# WX0_010_981DL_1.net
KiCad netlist of a schematic drawn in Altium Designer
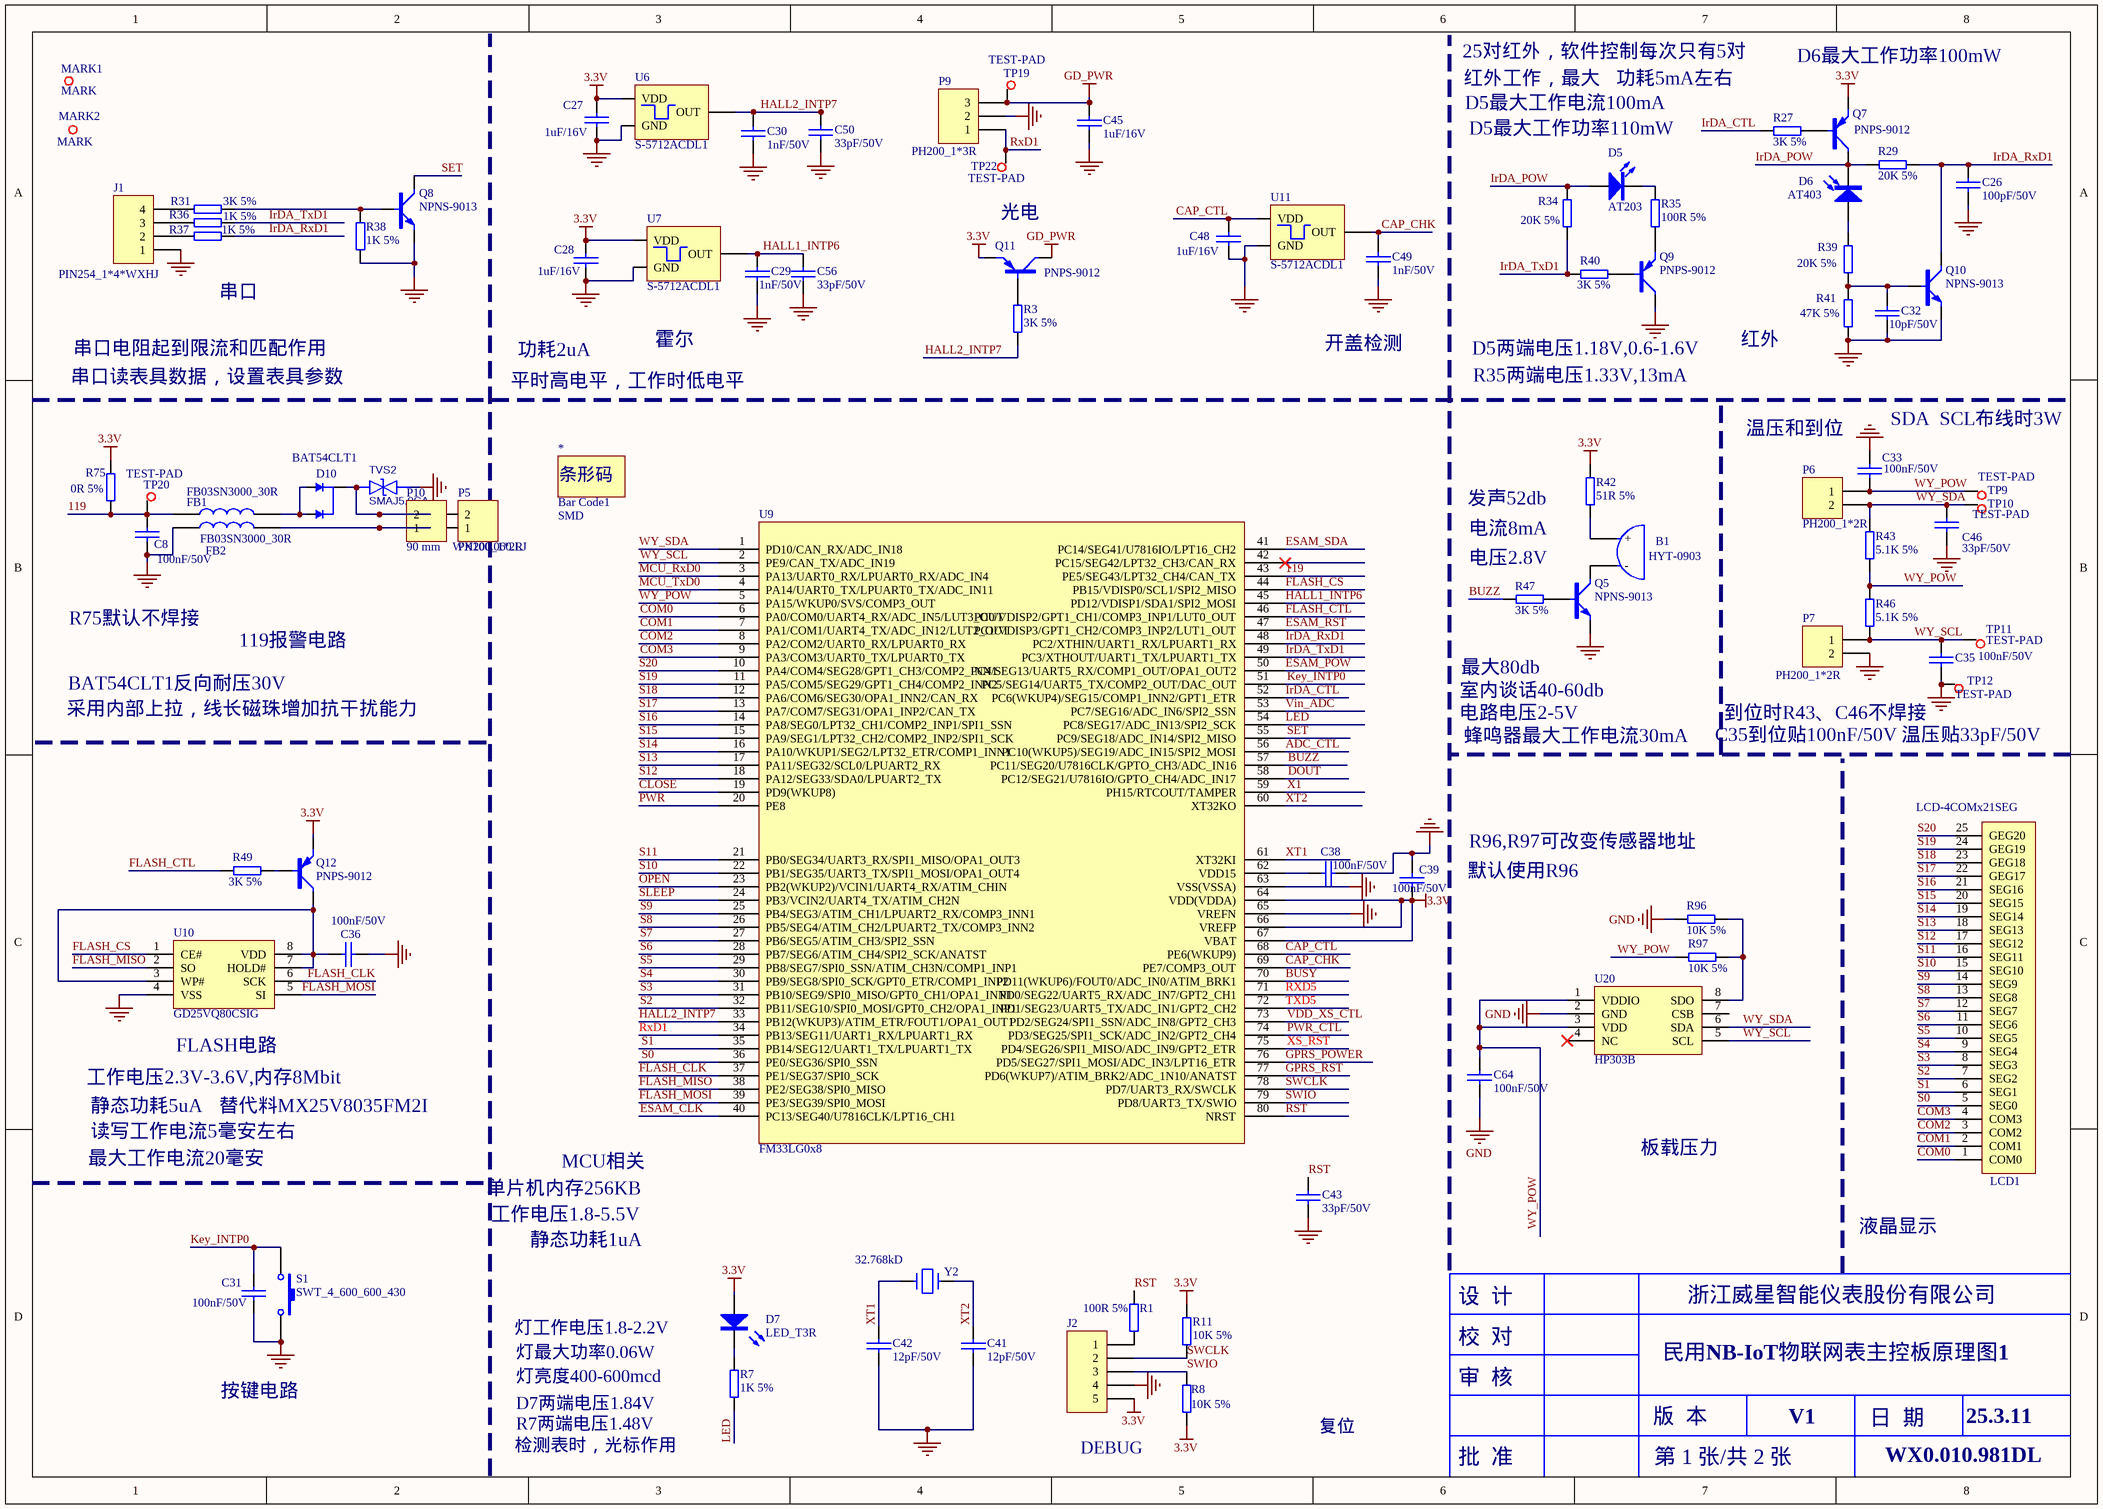
[diagram p0: WX0.010.981DL(1).SchDoc]

(export (version "E")
  (design (tool "Eeschema 10.0.6"))
  (components
    (comp (ref "*")
      (value "Bar Code1")
      (footprint "Bar Code1")
      (description "条形码 ,填充，无需焊接器件")
      (fields (field (name "PART NUMBER") "AD_WXHJ_Bar Code_02") (field (name "SMD/DIP") "SMD"))
      (libsource (lib "Database_Libs2") (part "05_AD_WXHJ_Bar Code_02"))
    )
    (comp (ref "B1")
      (value "HYT-0903")
      (footprint "HYT-0903")
      (description "直插,直径9mm,高5.5mm,5 V,2 V,30 mA,兴化市华宇电子有限公司,HYT-0903")
      (fields (field (name "PART NUMBER") "1010602-0007"))
      (libsource (lib "Database_Libs2") (part "07_HYT-0903"))
    )
    (comp (ref "C8")
      (value "100nF/50V")
      (footprint "CAP0603")
      (description "104pF,50 V,±10%,0603,国巨,CC0603KRX7R9BB104")
      (fields (field (name "PART NUMBER") "101020103-0021"))
      (libsource (lib "Database_Libs2") (part "CC03K7R9_100N"))
    )
    (comp (ref "C26")
      (value "100pF/50V")
      (footprint "CAP0603")
      (description "101pf,50 V,±5%,0603,国巨,CC0603JRNP09BN101")
      (fields (field (name "PART NUMBER") "101020103-0010"))
      (libsource (lib "Database_Libs2") (part "CC03JPO9_101P"))
    )
    (comp (ref "C27")
      (value "1uF/16V")
      (footprint "CAP0603")
      (description "105pF,16 V,±10%,0603,国巨,CC0603KRX7R7BB105")
      (fields (field (name "PART NUMBER") "101020103-0003"))
      (libsource (lib "Database_Libs2") (part "CC03K7R7_1U"))
    )
    (comp (ref "C28")
      (value "1uF/16V")
      (footprint "CAP0603")
      (description "105pF,16 V,±10%,0603,国巨,CC0603KRX7R7BB105")
      (fields (field (name "PART NUMBER") "101020103-0003"))
      (libsource (lib "Database_Libs2") (part "CC03K7R7_1U"))
    )
    (comp (ref "C29")
      (value "1nF/50V")
      (footprint "CAP0603")
      (description "102pF,50 V,±10%,0603,国巨,CC0603KRX7R9BB102")
      (fields (field (name "PART NUMBER") "101020103-0022"))
      (libsource (lib "Database_Libs2") (part "CC03K7R9_1N"))
    )
    (comp (ref "C30")
      (value "1nF/50V")
      (footprint "CAP0603")
      (description "102pF,50 V,±10%,0603,国巨,CC0603KRX7R9BB102")
      (fields (field (name "PART NUMBER") "101020103-0022"))
      (libsource (lib "Database_Libs2") (part "CC03K7R9_1N"))
    )
    (comp (ref "C31")
      (value "100nF/50V")
      (footprint "CAP0603")
      (description "104pF,50 V,±10%,0603,国巨,CC0603KRX7R9BB104")
      (fields (field (name "PART NUMBER") "101020103-0021"))
      (libsource (lib "Database_Libs2") (part "CC03K7R9_100N"))
    )
    (comp (ref "C32")
      (value "10pF/50V")
      (footprint "CAP0603")
      (description "10pF,50 V,±5%,0603,X7R,国巨,CC0603JRNPO9BN100")
      (fields (field (name "PART NUMBER") "101020103-0014"))
      (libsource (lib "Database_Libs2") (part "CC03JPO9_10P"))
    )
    (comp (ref "C33")
      (value "100nF/50V")
      (footprint "CAP0603")
      (description "104pF,50 V,±10%,0603,国巨,CC0603KRX7R9BB104")
      (fields (field (name "PART NUMBER") "101020103-0021"))
      (libsource (lib "Database_Libs2") (part "CC03K7R9_100N"))
    )
    (comp (ref "C35")
      (value "100nF/50V")
      (footprint "CAP0603")
      (description "104pF,50 V,±10%,0603,国巨,CC0603KRX7R9BB104")
      (fields (field (name "PART NUMBER") "101020103-0021"))
      (libsource (lib "Database_Libs2") (part "CC03K7R9_100N"))
    )
    (comp (ref "C36")
      (value "100nF/50V")
      (footprint "CAP0603")
      (description "104pF,50 V,±10%,0603,国巨,CC0603KRX7R9BB104")
      (fields (field (name "PART NUMBER") "101020103-0021"))
      (libsource (lib "Database_Libs2") (part "CC03K7R9_100N"))
    )
    (comp (ref "C38")
      (value "100nF/50V")
      (footprint "CAP0603")
      (description "104pF,50 V,±10%,0603,国巨,CC0603KRX7R9BB104")
      (fields (field (name "PART NUMBER") "101020103-0021"))
      (libsource (lib "Database_Libs2") (part "CC03K7R9_100N"))
    )
    (comp (ref "C39")
      (value "100nF/50V")
      (footprint "CAP0603")
      (description "104pF,50 V,±10%,0603,国巨,CC0603KRX7R9BB104")
      (fields (field (name "PART NUMBER") "101020103-0021"))
      (libsource (lib "Database_Libs2") (part "CC03K7R9_100N"))
    )
    (comp (ref "C41")
      (value "12pF/50V")
      (footprint "CAP0603")
      (description "12P,50 V,±5%,0603,国巨,CC0603JRNPO9BN12")
      (fields (field (name "PART NUMBER") "101020103-0005"))
      (libsource (lib "Database_Libs2") (part "CC03JPO9_12P"))
    )
    (comp (ref "C42")
      (value "12pF/50V")
      (footprint "CAP0603")
      (description "12P,50 V,±5%,0603,国巨,CC0603JRNPO9BN12")
      (fields (field (name "PART NUMBER") "101020103-0005"))
      (libsource (lib "Database_Libs2") (part "CC03JPO9_12P"))
    )
    (comp (ref "C43")
      (value "33pF/50V")
      (footprint "CAP0603")
      (description "33pF,50 V,±10%,0603,国巨,CC0603KRNPO9BN33")
      (fields (field (name "PART NUMBER") "101020103-0027"))
      (libsource (lib "Database_Libs2") (part "CC03KPO9_33P"))
    )
    (comp (ref "C45")
      (value "1uF/16V")
      (footprint "CAP0603")
      (description "105pF,16 V,±10%,0603,国巨,CC0603KRX7R7BB105")
      (fields (field (name "PART NUMBER") "101020103-0003"))
      (libsource (lib "Database_Libs2") (part "CC03K7R7_1U"))
    )
    (comp (ref "C46")
      (value "33pF/50V")
      (footprint "CAP0603")
      (description "33pF,50 V,±10%,0603,国巨,CC0603KRNPO9BN33")
      (fields (field (name "PART NUMBER") "101020103-0027"))
      (libsource (lib "Database_Libs2") (part "CC03KPO9_33P"))
    )
    (comp (ref "C48")
      (value "1uF/16V")
      (footprint "CAP0603")
      (description "105pF,16 V,±10%,0603,国巨,CC0603KRX7R7BB105")
      (fields (field (name "PART NUMBER") "101020103-0003"))
      (libsource (lib "Database_Libs2") (part "CC03K7R7_1U"))
    )
    (comp (ref "C49")
      (value "1nF/50V")
      (footprint "CAP0603")
      (description "102pF,50 V,±10%,0603,国巨,CC0603KRX7R9BB102")
      (fields (field (name "PART NUMBER") "101020103-0022"))
      (libsource (lib "Database_Libs2") (part "CC03K7R9_1N"))
    )
    (comp (ref "C50")
      (value "33pF/50V")
      (footprint "CAP0603")
      (description "33pF,50 V,±10%,0603,国巨,CC0603KRNPO9BN33")
      (fields (field (name "PART NUMBER") "101020103-0027"))
      (libsource (lib "Database_Libs2") (part "CC03KPO9_33P"))
    )
    (comp (ref "C56")
      (value "33pF/50V")
      (footprint "CAP0603")
      (description "33pF,50 V,±10%,0603,国巨,CC0603KRNPO9BN33")
      (fields (field (name "PART NUMBER") "101020103-0027"))
      (libsource (lib "Database_Libs2") (part "CC03KPO9_33P"))
    )
    (comp (ref "C64")
      (value "100nF/50V")
      (footprint "CAP0603")
      (description "104pF,50 V,±10%,0603,国巨,CC0603KRX7R9BB104")
      (fields (field (name "PART NUMBER") "101020103-0021"))
      (libsource (lib "Database_Libs2") (part "CC03K7R9_100N"))
    )
    (comp (ref "D5")
      (value "AT203")
      (footprint "IR_254_532_300")
      (description "DIP-2,φ3,插件,红光,上海品观电子有限公司/可得,AT203")
      (fields (field (name "PART NUMBER") "101040102-0010"))
      (libsource (lib "Database_Libs2") (part "01_AT203"))
    )
    (comp (ref "D6")
      (value "AT403")
      (footprint "IR_254_532_300")
      (description "DIP-2,φ3,插件,红光,上海品观电子有限公司/可得,AT403-PD-01")
      (fields (field (name "PART NUMBER") "101040102-0011"))
      (libsource (lib "Database_Libs2") (part "01_AT403"))
    )
    (comp (ref "D7")
      (value "LED_T3R")
      (footprint "LED2_300")
      (description "圆形插件,3mm 圆形,插件,红光,湖北匡通电子有限公司,3BB4HC")
      (fields (field (name "PART NUMBER") "101040102-0001"))
      (libsource (lib "Database_Libs2") (part "01-LED_T3R"))
    )
    (comp (ref "D10")
      (value "BAT54CLT1")
      (footprint "SOT-23")
      (description "BAT54CLT1，SOT23-3,SOT23-3,0.2 A,0.8 V,30 V,安森美,BAT54CLT1")
      (fields (field (name "PART NUMBER") "101040101-0038"))
      (libsource (lib "Database_Libs2") (part "02_BAT54CLT1"))
    )
    (comp (ref "FB1")
      (value "FB03SN3000_30R")
      (footprint "IND0603")
      (description "chilisin(奇力新),0603,30Ω ±25% @100MHz,150 V,125 ℃,PBY160808T-300Y-N,-55 ℃,不含铅,,,圆盘,30Ω ±25% @100MHz")
      (fields (field (name "PART NUMBER") "109010101-0003"))
      (libsource (lib "Database_Libs2") (part "06_FB03SN3000_30R"))
    )
    (comp (ref "FB2")
      (value "FB03SN3000_30R")
      (footprint "IND0603")
      (description "chilisin(奇力新),0603,30Ω ±25% @100MHz,150 V,125 ℃,PBY160808T-300Y-N,-55 ℃,不含铅,,,圆盘,30Ω ±25% @100MHz")
      (fields (field (name "PART NUMBER") "109010101-0003"))
      (libsource (lib "Database_Libs2") (part "06_FB03SN3000_30R"))
    )
    (comp (ref "J1")
      (value "PIN254_1*4*WXHJ")
      (footprint "PIN254_1*4*WXHJ")
      (description "1*4 ，Φ1.0 ，2.54mm，直脚,无需焊接器件")
      (fields (field (name "PART NUMBER") "AD_WXHJ_PinHeader_01"))
      (libsource (lib "Database_Libs2") (part "PIN254_1*4*WXHJ"))
    )
    (comp (ref "J2")
      (value "PIN254_1*5*WXHJ")
      (footprint "PIN254_1*5*WXHJ")
      (description "1*5 ，Φ1.0 ，2.54mm，直脚,无需焊接器件")
      (fields (field (name "PART NUMBER") "AD_WXHJ_PinHeader_02"))
      (libsource (lib "Database_Libs2") (part "PIN254_1*5*WXHJ"))
    )
    (comp (ref "LCD1")
      (value "GVH21861A-HPP")
      (footprint "LCD_GVH21861A-HPP")
      (fields (field (name "PART NUMBER") "1010801-0028") (field (name "SMD/DIP") "LCD-4COMx21SEG"))
      (libsource (lib "Database_Libs2") (part "03_LCD_GVH21861A-HPP"))
    )
    (comp (ref "MARK1")
      (value "MARK")
      (footprint "MARK")
      (description "MARK点")
      (fields (field (name "PART NUMBER") "AD_WXHJ_MARK_01"))
      (libsource (lib "Database_Libs2") (part "MARK"))
    )
    (comp (ref "MARK2")
      (value "MARK")
      (footprint "MARK")
      (description "MARK点")
      (fields (field (name "PART NUMBER") "AD_WXHJ_MARK_01"))
      (libsource (lib "Database_Libs2") (part "MARK"))
    )
    (comp (ref "P5")
      (value "PH200_1*2R")
      (description "2.0-2AW,直插弯座，2PIN，脚间距2mm，带防翘起,公头,单排,2.0-2AW;直插弯座，2PIN,脚间距2mm，带防翘起")
      (fields (field (name "PART NUMBER") "1010902-0105"))
      (libsource (lib "") (part "PH200_1*2R_1"))
    )
    (comp (ref "P6")
      (value "PH200_1*2R")
      (footprint "PH200_1*2R")
      (description "2.0-2AW,直插弯座，2PIN，脚间距2mm，带防翘起,公头,单排,2.0-2AW;直插弯座，2PIN,脚间距2mm，带防翘起")
      (fields (field (name "PART NUMBER") "1010902-0105"))
      (libsource (lib "Database_Libs2") (part "PH200_1*2R"))
    )
    (comp (ref "P7")
      (value "PH200_1*2R")
      (footprint "PH200_1*2R")
      (description "2.0-2AW,直插弯座，2PIN，脚间距2mm，带防翘起,公头,单排,2.0-2AW;直插弯座，2PIN,脚间距2mm，带防翘起")
      (fields (field (name "PART NUMBER") "1010902-0105"))
      (libsource (lib "Database_Libs2") (part "PH200_1*2R"))
    )
    (comp (ref "P9")
      (value "PH200_1*3R")
      (footprint "PH200_1*3R")
      (description "2.0-3AW,3PIN，2mm脚间距,公头,单排,2.0-3AW；3PIN，脚间距2mm直插弯座带防翘起")
      (fields (field (name "PART NUMBER") "1010902-0104"))
      (libsource (lib "Database_Libs2") (part "PH200_1*3R"))
    )
    (comp (ref "P10")
      (value "90 mm    WX100.060.LJ")
      (footprint "WXHJ_Connect_01")
      (description "电源连接线")
      (fields (field (name "PART NUMBER") "AD_WXHJ_Connect_01"))
      (libsource (lib "Database_Libs2") (part "WXHJ_Connect_01"))
    )
    (comp (ref "Q5")
      (value "NPNS-9013")
      (footprint "SOT-23")
      (description "9013,NPN,SOT-23,长电,S9013")
      (fields (field (name "PART NUMBER") "101040201-0002"))
      (libsource (lib "Database_Libs2") (part "03_NPNS-9013"))
    )
    (comp (ref "Q7")
      (value "PNPS-9012")
      (footprint "SOT-23")
      (description "9012,PNP,SOT-23,JCET;长电,S9012")
      (fields (field (name "PART NUMBER") "101040201-0001"))
      (libsource (lib "Database_Libs2") (part "03_PNPS-9012"))
    )
    (comp (ref "Q8")
      (value "NPNS-9013")
      (footprint "SOT-23")
      (description "9013,NPN,SOT-23,长电,S9013")
      (fields (field (name "PART NUMBER") "101040201-0002"))
      (libsource (lib "Database_Libs2") (part "03_NPNS-9013"))
    )
    (comp (ref "Q9")
      (value "PNPS-9012")
      (footprint "SOT-23")
      (description "9012,PNP,SOT-23,JCET;长电,S9012")
      (fields (field (name "PART NUMBER") "101040201-0001"))
      (libsource (lib "Database_Libs2") (part "03_PNPS-9012"))
    )
    (comp (ref "Q10")
      (value "NPNS-9013")
      (footprint "SOT-23")
      (description "9013,NPN,SOT-23,长电,S9013")
      (fields (field (name "PART NUMBER") "101040201-0002"))
      (libsource (lib "Database_Libs2") (part "03_NPNS-9013"))
    )
    (comp (ref "Q11")
      (value "PNPS-9012")
      (footprint "SOT-23")
      (description "9012,PNP,SOT-23,JCET;长电,S9012")
      (fields (field (name "PART NUMBER") "101040201-0001"))
      (libsource (lib "Database_Libs2") (part "03_PNPS-9012"))
    )
    (comp (ref "Q12")
      (value "PNPS-9012")
      (footprint "SOT-23")
      (description "9012,PNP,SOT-23,JCET;长电,S9012")
      (fields (field (name "PART NUMBER") "101040201-0001"))
      (libsource (lib "Database_Libs2") (part "03_PNPS-9012"))
    )
    (comp (ref "R1")
      (value "100R 5%")
      (footprint "RES0603")
      (description "100R,±5%,1/10W,0603,国巨,RC0603JR-07100RL")
      (fields (field (name "PART NUMBER") "101010103-0022"))
      (libsource (lib "Database_Libs2") (part "RC03J_100R"))
    )
    (comp (ref "R3")
      (value "3K 5%")
      (footprint "RES0603")
      (description "国巨,±5%,0603,,155 ℃,-55 ℃,RC0603JR-073KL,无铅,100 ppm/℃,1/10W,,3K")
      (fields (field (name "PART NUMBER") "101010103-0006"))
      (libsource (lib "Database_Libs2") (part "RC03J_3K"))
    )
    (comp (ref "R7")
      (value "1K 5%")
      (footprint "RES0603")
      (description "1K,±5%,1/10W,0603,国巨,RC0603JR-071KL")
      (fields (field (name "PART NUMBER") "101010103-0008"))
      (libsource (lib "Database_Libs2") (part "RC03J_1K"))
    )
    (comp (ref "R8")
      (value "10K 5%")
      (footprint "RES0603")
      (description "国巨,±5%,0603,,155 ℃,-55 ℃,RC0603JR-0710KL,无铅,200 ppm/℃,1/10W,,10K")
      (fields (field (name "PART NUMBER") "101010103-0003"))
      (libsource (lib "Database_Libs2") (part "RC03J_10K"))
    )
    (comp (ref "R11")
      (value "10K 5%")
      (footprint "RES0603")
      (description "国巨,±5%,0603,,155 ℃,-55 ℃,RC0603JR-0710KL,无铅,200 ppm/℃,1/10W,,10K")
      (fields (field (name "PART NUMBER") "101010103-0003"))
      (libsource (lib "Database_Libs2") (part "RC03J_10K"))
    )
    (comp (ref "R27")
      (value "3K 5%")
      (footprint "RES0603")
      (description "国巨,±5%,0603,,155 ℃,-55 ℃,RC0603JR-073KL,无铅,100 ppm/℃,1/10W,,3K")
      (fields (field (name "PART NUMBER") "101010103-0006"))
      (libsource (lib "Database_Libs2") (part "RC03J_3K"))
    )
    (comp (ref "R29")
      (value "20K 5%")
      (footprint "RES0603")
      (description "国巨,±5%,0603,,155 ℃,-55 ℃,RC0603JR-0720KL,无铅,200 ppm/℃,1/10W,,20K")
      (fields (field (name "PART NUMBER") "101010103-0004"))
      (libsource (lib "Database_Libs2") (part "RC03J_20K"))
    )
    (comp (ref "R31")
      (value "3K 5%")
      (footprint "RES0603")
      (description "国巨,±5%,0603,,155 ℃,-55 ℃,RC0603JR-073KL,无铅,100 ppm/℃,1/10W,,3K")
      (fields (field (name "PART NUMBER") "101010103-0006"))
      (libsource (lib "Database_Libs2") (part "RC03J_3K"))
    )
    (comp (ref "R34")
      (value "20K 5%")
      (footprint "RES0603")
      (description "国巨,±5%,0603,,155 ℃,-55 ℃,RC0603JR-0720KL,无铅,200 ppm/℃,1/10W,,20K")
      (fields (field (name "PART NUMBER") "101010103-0004"))
      (libsource (lib "Database_Libs2") (part "RC03J_20K"))
    )
    (comp (ref "R35")
      (value "100R 5%")
      (footprint "RES0603")
      (description "100R,±5%,1/10W,0603,国巨,RC0603JR-07100RL")
      (fields (field (name "PART NUMBER") "101010103-0022"))
      (libsource (lib "Database_Libs2") (part "RC03J_100R"))
    )
    (comp (ref "R36")
      (value "1K 5%")
      (footprint "RES0603")
      (description "1K,±5%,1/10W,0603,国巨,RC0603JR-071KL")
      (fields (field (name "PART NUMBER") "101010103-0008"))
      (libsource (lib "Database_Libs2") (part "RC03J_1K"))
    )
    (comp (ref "R37")
      (value "1K 5%")
      (footprint "RES0603")
      (description "1K,±5%,1/10W,0603,国巨,RC0603JR-071KL")
      (fields (field (name "PART NUMBER") "101010103-0008"))
      (libsource (lib "Database_Libs2") (part "RC03J_1K"))
    )
    (comp (ref "R38")
      (value "1K 5%")
      (footprint "RES0603")
      (description "1K,±5%,1/10W,0603,国巨,RC0603JR-071KL")
      (fields (field (name "PART NUMBER") "101010103-0008"))
      (libsource (lib "Database_Libs2") (part "RC03J_1K"))
    )
    (comp (ref "R39")
      (value "20K 5%")
      (footprint "RES0603")
      (description "国巨,±5%,0603,,155 ℃,-55 ℃,RC0603JR-0720KL,无铅,200 ppm/℃,1/10W,,20K")
      (fields (field (name "PART NUMBER") "101010103-0004"))
      (libsource (lib "Database_Libs2") (part "RC03J_20K"))
    )
    (comp (ref "R40")
      (value "3K 5%")
      (footprint "RES0603")
      (description "国巨,±5%,0603,,155 ℃,-55 ℃,RC0603JR-073KL,无铅,100 ppm/℃,1/10W,,3K")
      (fields (field (name "PART NUMBER") "101010103-0006"))
      (libsource (lib "Database_Libs2") (part "RC03J_3K"))
    )
    (comp (ref "R41")
      (value "47K 5%")
      (footprint "RES0603")
      (description "47K,±5%,1/10W,0603,国巨,RC0603JR-0747KL")
      (fields (field (name "PART NUMBER") "101010103-0012"))
      (libsource (lib "Database_Libs2") (part "RC03J_47K"))
    )
    (comp (ref "R42")
      (value "51R 5%")
      (footprint "RES0603")
      (description "国巨,±5%,0603,,155 ℃,-55 ℃,RC0603JR-0751RL,无铅,100 ppm/℃,1/10W,,51欧")
      (fields (field (name "PART NUMBER") "101010103-0037"))
      (libsource (lib "Database_Libs2") (part "RC03J_51R"))
    )
    (comp (ref "R43")
      (value "5.1K 5%")
      (footprint "RES0603")
      (description "国巨,±5%,0603,,155 ℃,55 ℃,RC0603JR-075.1KL,无铅,200 ppm/℃,1/10W,,5.1k")
      (fields (field (name "PART NUMBER") "101010103-0015"))
      (libsource (lib "Database_Libs2") (part "RC03J_5.1K"))
    )
    (comp (ref "R46")
      (value "5.1K 5%")
      (footprint "RES0603")
      (description "国巨,±5%,0603,,155 ℃,55 ℃,RC0603JR-075.1KL,无铅,200 ppm/℃,1/10W,,5.1k")
      (fields (field (name "PART NUMBER") "101010103-0015"))
      (libsource (lib "Database_Libs2") (part "RC03J_5.1K"))
    )
    (comp (ref "R47")
      (value "3K 5%")
      (footprint "RES0603")
      (description "国巨,±5%,0603,,155 ℃,-55 ℃,RC0603JR-073KL,无铅,100 ppm/℃,1/10W,,3K")
      (fields (field (name "PART NUMBER") "101010103-0006"))
      (libsource (lib "Database_Libs2") (part "RC03J_3K"))
    )
    (comp (ref "R49")
      (value "3K 5%")
      (footprint "RES0603")
      (description "国巨,±5%,0603,,155 ℃,-55 ℃,RC0603JR-073KL,无铅,100 ppm/℃,1/10W,,3K")
      (fields (field (name "PART NUMBER") "101010103-0006"))
      (libsource (lib "Database_Libs2") (part "RC03J_3K"))
    )
    (comp (ref "R75")
      (value "0R 5%")
      (description "0Ω,±5%,1/4W,1206,国巨,RC1206JR-070RL")
      (fields (field (name "PART NUMBER") "101010101-0013"))
      (libsource (lib "Database_Libs2") (part "RC06J_0R"))
    )
    (comp (ref "R96")
      (value "10K 5%")
      (footprint "RES0603")
      (description "国巨,±5%,0603,,155 ℃,-55 ℃,RC0603JR-071ML,无铅,200 ppm/℃,1/10W,,1M")
      (fields (field (name "PART NUMBER") "101010103-0002"))
      (libsource (lib "Database_Libs2") (part "RC03J_1M"))
    )
    (comp (ref "R97")
      (value "10K 5%")
      (footprint "RES0603")
      (description "国巨,±5%,0603,,155 ℃,-55 ℃,RC0603JR-071ML,无铅,200 ppm/℃,1/10W,,1M")
      (fields (field (name "PART NUMBER") "101010103-0002"))
      (libsource (lib "Database_Libs2") (part "RC03J_1M"))
    )
    (comp (ref "S1")
      (value "SWT_4_600_600_430")
      (footprint "SWT_4_600_600")
      (description "TS-1102,机械轻触,6*6*4.3直插,6*6*4.3直插,乐清市羽欧电子")
      (fields (field (name "PART NUMBER") "1011001-0027"))
      (libsource (lib "Database_Libs2") (part "07_SWT_4_600_600_430"))
    )
    (comp (ref "TP9")
      (value "TEST-PAD")
      (footprint "TEST-PAD")
      (description "单面焊盘测试点")
      (fields (field (name "PART NUMBER") "AD_WXHJ_TEST-PAD_01"))
      (libsource (lib "Database_Libs2") (part "TEST-PAD"))
    )
    (comp (ref "TP10")
      (value "TEST-PAD")
      (footprint "TEST-PAD")
      (description "单面焊盘测试点")
      (fields (field (name "PART NUMBER") "AD_WXHJ_TEST-PAD_01"))
      (libsource (lib "Database_Libs2") (part "TEST-PAD"))
    )
    (comp (ref "TP11")
      (value "TEST-PAD")
      (footprint "TEST-PAD")
      (description "单面焊盘测试点")
      (fields (field (name "PART NUMBER") "AD_WXHJ_TEST-PAD_01"))
      (libsource (lib "Database_Libs2") (part "TEST-PAD"))
    )
    (comp (ref "TP12")
      (value "TEST-PAD")
      (footprint "TEST-PAD")
      (description "单面焊盘测试点")
      (fields (field (name "PART NUMBER") "AD_WXHJ_TEST-PAD_01"))
      (libsource (lib "Database_Libs2") (part "TEST-PAD"))
    )
    (comp (ref "TP19")
      (value "TEST-PAD")
      (footprint "TEST-PAD")
      (description "单面焊盘测试点")
      (fields (field (name "PART NUMBER") "AD_WXHJ_TEST-PAD_01"))
      (libsource (lib "Database_Libs2") (part "TEST-PAD"))
    )
    (comp (ref "TP20")
      (value "TEST-PAD")
      (footprint "TEST-PAD")
      (description "单面焊盘测试点")
      (fields (field (name "PART NUMBER") "AD_WXHJ_TEST-PAD_01"))
      (libsource (lib "Database_Libs2") (part "TEST-PAD"))
    )
    (comp (ref "TP22")
      (value "TEST-PAD")
      (footprint "TEST-PAD")
      (description "单面焊盘测试点")
      (fields (field (name "PART NUMBER") "AD_WXHJ_TEST-PAD_01"))
      (libsource (lib "Database_Libs2") (part "TEST-PAD"))
    )
    (comp (ref "TVS2")
      (value "SMAJ5.0CA")
      (footprint "SMAJ5.0CA")
      (fields (field (name "BOM_SUPPLIER PART") "C693487") (field (name "CONTRIBUTOR") "LCSC"))
      (libsource (lib "Discrete_WX") (part "SMAJ5.0CA_C693487"))
    )
    (comp (ref "U6")
      (value "S-5712ACDL1")
      (footprint "SOT-23")
      (description "S-5712ACDL1,SOT23-3,3.5 V,1.6 V,2 uA,精工电子,S-5712ACDL1")
      (fields (field (name "PART NUMBER") "1010504-0002"))
      (libsource (lib "Database_Libs2") (part "01_S-5712ACDL1"))
    )
    (comp (ref "U7")
      (value "S-5712ACDL1")
      (footprint "SOT-23")
      (description "S-5712ACDL1,SOT23-3,3.5 V,1.6 V,2 uA,精工电子,S-5712ACDL1")
      (fields (field (name "PART NUMBER") "1010504-0002"))
      (libsource (lib "Database_Libs2") (part "01_S-5712ACDL1"))
    )
    (comp (ref "U9") (value "FM33LG0x8") (footprint "LQFP80") (libsource (lib "FM_MCU") (part "FM33LG0x8")))
    (comp (ref "U10")
      (value "GD25VQ80CSIG")
      (footprint "SOP-8L-200MIL")
      (description "GD25VQ80CSIG,SOP8 208mil,北京兆易创新科技股份有限公司,GD25VQ80CSIG")
      (fields (field (name "PART NUMBER") "101050101-0165"))
      (libsource (lib "Database_Libs2") (part "04_GD25VQ80CSIG"))
    )
    (comp (ref "U11")
      (value "S-5712ACDL1")
      (footprint "SOT-23")
      (description "S-5712ACDL1,SOT23-3,3.5 V,1.6 V,2 uA,精工电子,S-5712ACDL1")
      (fields (field (name "PART NUMBER") "1010504-0002"))
      (libsource (lib "Database_Libs2") (part "01_S-5712ACDL1"))
    )
    (comp (ref "U20") (value "HP303B") (footprint "LGA_8") (libsource (lib "Schlib2") (part "HP303B")))
    (comp (ref "Y2")
      (value "32.768kD")
      (footprint "SMD-3215_2P")
      (fields (field (name "PART NUMBER") "1010601-0020"))
      (libsource (lib "Database_Libs2") (part "04_XTALSG12MD_32.768kD"))
    )
  )
  (nets
    (net (code "1") (name "/119") (class "Default")
      (node (ref "C8") (pin "1") (pinfunction "1_1") (pintype "passive"))
      (node (ref "FB1") (pin "1") (pinfunction "1_1") (pintype "passive"))
      (node (ref "R75") (pin "1") (pinfunction "1_1") (pintype "passive"))
      (node (ref "TP20") (pin "1") (pinfunction "1_1") (pintype "passive"))
      (node (ref "U9") (pin "43") (pinfunction "PE5/SEG43/LPT32_CH4/CAN_TX_43") (pintype "passive"))
    )
    (net (code "2") (name "/ADC_CTL") (class "Default")
      (node (ref "U9") (pin "56") (pinfunction "PC10(WKUP5)/SEG19/ADC_IN15/SPI2_MOSI_56") (pintype "passive"))
    )
    (net (code "3") (name "/BUSY") (class "Default")
      (node (ref "U9") (pin "70") (pinfunction "PD11(WKUP6)/FOUT0/ADC_IN0/ATIM_BRK1_70") (pintype "passive"))
    )
    (net (code "4") (name "/BUZZ") (class "Default")
      (node (ref "R47") (pin "1") (pinfunction "1_1") (pintype "passive"))
      (node (ref "U9") (pin "57") (pinfunction "PC11/SEG20/U7816CLK/GPTO_CH3/ADC_IN16_57") (pintype "passive"))
    )
    (net (code "5") (name "/CAP_CHK") (class "Default")
      (node (ref "C49") (pin "1") (pinfunction "1_1") (pintype "passive"))
      (node (ref "U11") (pin "2") (pinfunction "OUT_2") (pintype "passive"))
      (node (ref "U9") (pin "69") (pinfunction "PE7/COMP3_OUT_69") (pintype "passive"))
    )
    (net (code "6") (name "/CAP_CTL") (class "Default")
      (node (ref "C48") (pin "1") (pinfunction "1_1") (pintype "passive"))
      (node (ref "U11") (pin "1") (pinfunction "VDD_1") (pintype "passive"))
      (node (ref "U9") (pin "68") (pinfunction "PE6(WKUP9)_68") (pintype "passive"))
    )
    (net (code "7") (name "/CLOSE") (class "Default")
      (node (ref "U9") (pin "19") (pinfunction "PD9(WKUP8)_19") (pintype "passive"))
    )
    (net (code "8") (name "/COM0") (class "Default")
      (node (ref "LCD1") (pin "1") (pinfunction "COM0_1") (pintype "passive"))
      (node (ref "U9") (pin "6") (pinfunction "PA0/COM0/UART4_RX/ADC_IN5/LUT3_OUT_6") (pintype "passive"))
    )
    (net (code "9") (name "/COM1") (class "Default")
      (node (ref "LCD1") (pin "2") (pinfunction "COM1_2") (pintype "passive"))
      (node (ref "U9") (pin "7") (pinfunction "PA1/COM1/UART4_TX/ADC_IN12/LUT2_OUT_7") (pintype "passive"))
    )
    (net (code "10") (name "/COM2") (class "Default")
      (node (ref "LCD1") (pin "3") (pinfunction "COM2_3") (pintype "passive"))
      (node (ref "U9") (pin "8") (pinfunction "PA2/COM2/UART0_RX/LPUART0_RX_8") (pintype "passive"))
    )
    (net (code "11") (name "/COM3") (class "Default")
      (node (ref "LCD1") (pin "4") (pinfunction "COM3_4") (pintype "passive"))
      (node (ref "U9") (pin "9") (pinfunction "PA3/COM3/UART0_TX/LPUART0_TX_9") (pintype "passive"))
    )
    (net (code "12") (name "/DOUT") (class "Default")
      (node (ref "U9") (pin "58") (pinfunction "PC12/SEG21/U7816IO/GPTO_CH4/ADC_IN17_58") (pintype "passive"))
    )
    (net (code "13") (name "/ESAM_CLK") (class "Default")
      (node (ref "U9") (pin "40") (pinfunction "PC13/SEG40/U7816CLK/LPT16_CH1_40") (pintype "passive"))
    )
    (net (code "14") (name "/ESAM_POW") (class "Default")
      (node (ref "U9") (pin "50") (pinfunction "PC4/SEG13/UART5_RX/COMP1_OUT/OPA1_OUT2_50") (pintype "passive"))
    )
    (net (code "15") (name "/ESAM_RST") (class "Default")
      (node (ref "U9") (pin "47") (pinfunction "PC1/VDISP3/GPT1_CH2/COMP3_INP2/LUT1_OUT_47") (pintype "passive"))
    )
    (net (code "16") (name "/ESAM_SDA") (class "Default")
      (node (ref "U9") (pin "41") (pinfunction "PC14/SEG41/U7816IO/LPT16_CH2_41") (pintype "passive"))
    )
    (net (code "17") (name "/FLASH_CLK") (class "Default")
      (node (ref "U10") (pin "6") (pinfunction "SCK_6") (pintype "passive"))
      (node (ref "U9") (pin "37") (pinfunction "PE1/SEG37/SPI0_SCK_37") (pintype "passive"))
    )
    (net (code "18") (name "/FLASH_CS") (class "Default")
      (node (ref "U10") (pin "1") (pinfunction "CE#_1") (pintype "passive"))
      (node (ref "U9") (pin "44") (pinfunction "PB15/VDISP0/SCL1/SPI2_MISO_44") (pintype "passive"))
    )
    (net (code "19") (name "/FLASH_CTL") (class "Default")
      (node (ref "R49") (pin "1") (pinfunction "1_1") (pintype "passive"))
      (node (ref "U9") (pin "46") (pinfunction "PC0/VDISP2/GPT1_CH1/COMP3_INP1/LUT0_OUT_46") (pintype "passive"))
    )
    (net (code "20") (name "/FLASH_MISO") (class "Default")
      (node (ref "U10") (pin "2") (pinfunction "SO_2") (pintype "passive"))
      (node (ref "U9") (pin "38") (pinfunction "PE2/SEG38/SPI0_MISO_38") (pintype "passive"))
    )
    (net (code "21") (name "/FLASH_MOSI") (class "Default")
      (node (ref "U10") (pin "5") (pinfunction "SI_5") (pintype "passive"))
      (node (ref "U9") (pin "39") (pinfunction "PE3/SEG39/SPI0_MOSI_39") (pintype "passive"))
    )
    (net (code "22") (name "/GPRS_POWER") (class "Default")
      (node (ref "U9") (pin "76") (pinfunction "PD5/SEG27/SPI1_MOSI/ADC_IN3/LPT16_ETR_76") (pintype "passive"))
    )
    (net (code "23") (name "/GPRS_RST") (class "Default")
      (node (ref "U9") (pin "77") (pinfunction "PD6(WKUP7)/ATIM_BRK2/ADC_1N10/ANATST_77") (pintype "passive"))
    )
    (net (code "24") (name "/HALL1_INTP6") (class "Default")
      (node (ref "C29") (pin "1") (pinfunction "1_1") (pintype "passive"))
      (node (ref "C56") (pin "1") (pinfunction "1_1") (pintype "passive"))
      (node (ref "U7") (pin "2") (pinfunction "OUT_2") (pintype "passive"))
      (node (ref "U9") (pin "45") (pinfunction "PD12/VDISP1/SDA1/SPI2_MOSI_45") (pintype "passive"))
    )
    (net (code "25") (name "/HALL2_INTP7") (class "Default")
      (node (ref "C30") (pin "1") (pinfunction "1_1") (pintype "passive"))
      (node (ref "C50") (pin "1") (pinfunction "1_1") (pintype "passive"))
      (node (ref "R3") (pin "1") (pinfunction "1_1") (pintype "passive"))
      (node (ref "U6") (pin "2") (pinfunction "OUT_2") (pintype "passive"))
      (node (ref "U9") (pin "33") (pinfunction "PB12(WKUP3)/ATIM_ETR/FOUT1/OPA1_OUT1_33") (pintype "passive"))
    )
    (net (code "26") (name "/IrDA_CTL") (class "Default")
      (node (ref "R27") (pin "1") (pinfunction "1_1") (pintype "passive"))
      (node (ref "U9") (pin "52") (pinfunction "PC6(WKUP4)/SEG15/COMP1_INN2/GPT1_ETR_52") (pintype "passive"))
    )
    (net (code "27") (name "/IrDA_POW") (class "Default")
      (node (ref "D5") (pin "1") (pinfunction "A_1") (pintype "passive"))
      (node (ref "D6") (pin "2") (pinfunction "K_2") (pintype "passive"))
      (node (ref "Q7") (pin "3") (pinfunction "C_3") (pintype "passive"))
      (node (ref "R29") (pin "1") (pinfunction "1_1") (pintype "passive"))
      (node (ref "R34") (pin "2") (pinfunction "2_2") (pintype "passive"))
    )
    (net (code "28") (name "/IrDA_RxD1") (class "Default")
      (node (ref "C26") (pin "1") (pinfunction "1_1") (pintype "passive"))
      (node (ref "Q10") (pin "3") (pinfunction "C_3") (pintype "passive"))
      (node (ref "R29") (pin "2") (pinfunction "2_2") (pintype "passive"))
      (node (ref "R37") (pin "2") (pinfunction "2_2") (pintype "passive"))
      (node (ref "U9") (pin "48") (pinfunction "PC2/XTHIN/UART1_RX/LPUART1_RX_48") (pintype "passive"))
    )
    (net (code "29") (name "/IrDA_TxD1") (class "Default")
      (node (ref "R34") (pin "1") (pinfunction "1_1") (pintype "passive"))
      (node (ref "R36") (pin "2") (pinfunction "2_2") (pintype "passive"))
      (node (ref "R40") (pin "1") (pinfunction "1_1") (pintype "passive"))
      (node (ref "U9") (pin "49") (pinfunction "PC3/XTHOUT/UART1_TX/LPUART1_TX_49") (pintype "passive"))
    )
    (net (code "30") (name "/Key_INTP0") (class "Default")
      (node (ref "C31") (pin "1") (pinfunction "1_1") (pintype "passive"))
      (node (ref "S1") (pin "1") (pinfunction "1_1") (pintype "passive"))
      (node (ref "U9") (pin "51") (pinfunction "PC5/SEG14/UART5_TX/COMP2_OUT/DAC_OUT_51") (pintype "passive"))
    )
    (net (code "31") (name "/LED") (class "Default")
      (node (ref "R7") (pin "1") (pinfunction "1_1") (pintype "passive"))
      (node (ref "U9") (pin "54") (pinfunction "PC8/SEG17/ADC_IN13/SPI2_SCK_54") (pintype "passive"))
    )
    (net (code "32") (name "/MCU_RxD0") (class "Default")
      (node (ref "U9") (pin "3") (pinfunction "PA13/UART0_RX/LPUART0_RX/ADC_IN4_3") (pintype "passive"))
    )
    (net (code "33") (name "/MCU_TxD0") (class "Default")
      (node (ref "U9") (pin "4") (pinfunction "PA14/UART0_TX/LPUART0_TX/ADC_IN11_4") (pintype "passive"))
    )
    (net (code "34") (name "/OPEN") (class "Default")
      (node (ref "U9") (pin "23") (pinfunction "PB2(WKUP2)/VCIN1/UART4_RX/ATIM_CHIN_23") (pintype "passive"))
    )
    (net (code "35") (name "/PWR") (class "Default")
      (node (ref "U9") (pin "20") (pinfunction "PE8_20") (pintype "passive"))
    )
    (net (code "36") (name "/PWR_CTL") (class "Default")
      (node (ref "U9") (pin "74") (pinfunction "PD3/SEG25/SPI1_SCK/ADC_IN2/GPT2_CH4_74") (pintype "passive"))
    )
    (net (code "37") (name "/RST") (class "Default")
      (node (ref "C43") (pin "1") (pinfunction "1_1") (pintype "passive"))
      (node (ref "R1") (pin "1") (pinfunction "1_1") (pintype "passive"))
      (node (ref "U9") (pin "80") (pinfunction "NRST_80") (pintype "passive"))
    )
    (net (code "38") (name "/RXD5") (class "Default")
      (node (ref "U9") (pin "71") (pinfunction "PD0/SEG22/UART5_RX/ADC_IN7/GPT2_CH1_71") (pintype "passive"))
    )
    (net (code "39") (name "/RxD1") (class "Default")
      (node (ref "P9") (pin "1") (pinfunction "1_1") (pintype "passive"))
      (node (ref "TP22") (pin "1") (pinfunction "1_1") (pintype "passive"))
      (node (ref "U9") (pin "34") (pinfunction "PB13/SEG11/UART1_RX/LPUART1_RX_34") (pintype "passive"))
    )
    (net (code "40") (name "/S0") (class "Default")
      (node (ref "LCD1") (pin "5") (pinfunction "SEG0_5") (pintype "passive"))
      (node (ref "U9") (pin "36") (pinfunction "PE0/SEG36/SPI0_SSN_36") (pintype "passive"))
    )
    (net (code "41") (name "/S1") (class "Default")
      (node (ref "LCD1") (pin "6") (pinfunction "SEG1_6") (pintype "passive"))
      (node (ref "U9") (pin "35") (pinfunction "PB14/SEG12/UART1_TX/LPUART1_TX_35") (pintype "passive"))
    )
    (net (code "42") (name "/S2") (class "Default")
      (node (ref "LCD1") (pin "7") (pinfunction "SEG2_7") (pintype "passive"))
      (node (ref "U9") (pin "32") (pinfunction "PB11/SEG10/SPI0_MOSI/GPT0_CH2/OPA1_INP1_32") (pintype "passive"))
    )
    (net (code "43") (name "/S3") (class "Default")
      (node (ref "LCD1") (pin "8") (pinfunction "SEG3_8") (pintype "passive"))
      (node (ref "U9") (pin "31") (pinfunction "PB10/SEG9/SPI0_MISO/GPT0_CH1/OPA1_INN1_31") (pintype "passive"))
    )
    (net (code "44") (name "/S4") (class "Default")
      (node (ref "LCD1") (pin "9") (pinfunction "SEG4_9") (pintype "passive"))
      (node (ref "U9") (pin "30") (pinfunction "PB9/SEG8/SPI0_SCK/GPT0_ETR/COMP1_INP2_30") (pintype "passive"))
    )
    (net (code "45") (name "/S5") (class "Default")
      (node (ref "LCD1") (pin "10") (pinfunction "SEG5_10") (pintype "passive"))
      (node (ref "U9") (pin "29") (pinfunction "PB8/SEG7/SPI0_SSN/ATIM_CH3N/COMP1_INP1_29") (pintype "passive"))
    )
    (net (code "46") (name "/S6") (class "Default")
      (node (ref "LCD1") (pin "11") (pinfunction "SEG6_11") (pintype "passive"))
      (node (ref "U9") (pin "28") (pinfunction "PB7/SEG6/ATIM_CH4/SPI2_SCK/ANATST_28") (pintype "passive"))
    )
    (net (code "47") (name "/S7") (class "Default")
      (node (ref "LCD1") (pin "12") (pinfunction "SEG7_12") (pintype "passive"))
      (node (ref "U9") (pin "27") (pinfunction "PB6/SEG5/ATIM_CH3/SPI2_SSN_27") (pintype "passive"))
    )
    (net (code "48") (name "/S8") (class "Default")
      (node (ref "LCD1") (pin "13") (pinfunction "SEG8_13") (pintype "passive"))
      (node (ref "U9") (pin "26") (pinfunction "PB5/SEG4/ATIM_CH2/LPUART2_TX/COMP3_INN2_26") (pintype "passive"))
    )
    (net (code "49") (name "/S9") (class "Default")
      (node (ref "LCD1") (pin "14") (pinfunction "SEG9_14") (pintype "passive"))
      (node (ref "U9") (pin "25") (pinfunction "PB4/SEG3/ATIM_CH1/LPUART2_RX/COMP3_INN1_25") (pintype "passive"))
    )
    (net (code "50") (name "/S10") (class "Default")
      (node (ref "LCD1") (pin "15") (pinfunction "SEG10_15") (pintype "passive"))
      (node (ref "U9") (pin "22") (pinfunction "PB1/SEG35/UART3_TX/SPI1_MOSI/OPA1_OUT4_22") (pintype "passive"))
    )
    (net (code "51") (name "/S11") (class "Default")
      (node (ref "LCD1") (pin "16") (pinfunction "SEG11_16") (pintype "passive"))
      (node (ref "U9") (pin "21") (pinfunction "PB0/SEG34/UART3_RX/SPI1_MISO/OPA1_OUT3_21") (pintype "passive"))
    )
    (net (code "52") (name "/S12") (class "Default")
      (node (ref "LCD1") (pin "17") (pinfunction "SEG12_17") (pintype "passive"))
      (node (ref "U9") (pin "18") (pinfunction "PA12/SEG33/SDA0/LPUART2_TX_18") (pintype "passive"))
    )
    (net (code "53") (name "/S13") (class "Default")
      (node (ref "LCD1") (pin "18") (pinfunction "SEG13_18") (pintype "passive"))
      (node (ref "U9") (pin "17") (pinfunction "PA11/SEG32/SCL0/LPUART2_RX_17") (pintype "passive"))
    )
    (net (code "54") (name "/S14") (class "Default")
      (node (ref "LCD1") (pin "19") (pinfunction "SEG14_19") (pintype "passive"))
      (node (ref "U9") (pin "16") (pinfunction "PA10/WKUP1/SEG2/LPT32_ETR/COMP1_INN1_16") (pintype "passive"))
    )
    (net (code "55") (name "/S15") (class "Default")
      (node (ref "LCD1") (pin "20") (pinfunction "SEG15_20") (pintype "passive"))
      (node (ref "U9") (pin "15") (pinfunction "PA9/SEG1/LPT32_CH2/COMP2_INP2/SPI1_SCK_15") (pintype "passive"))
    )
    (net (code "56") (name "/S16") (class "Default")
      (node (ref "LCD1") (pin "21") (pinfunction "SEG16_21") (pintype "passive"))
      (node (ref "U9") (pin "14") (pinfunction "PA8/SEG0/LPT32_CH1/COMP2_INP1/SPI1_SSN_14") (pintype "passive"))
    )
    (net (code "57") (name "/S17") (class "Default")
      (node (ref "LCD1") (pin "22") (pinfunction "GEG17_22") (pintype "passive"))
      (node (ref "U9") (pin "13") (pinfunction "PA7/COM7/SEG31/OPA1_INP2/CAN_TX_13") (pintype "passive"))
    )
    (net (code "58") (name "/S18") (class "Default")
      (node (ref "LCD1") (pin "23") (pinfunction "GEG18_23") (pintype "passive"))
      (node (ref "U9") (pin "12") (pinfunction "PA6/COM6/SEG30/OPA1_INN2/CAN_RX_12") (pintype "passive"))
    )
    (net (code "59") (name "/S19") (class "Default")
      (node (ref "LCD1") (pin "24") (pinfunction "GEG19_24") (pintype "passive"))
      (node (ref "U9") (pin "11") (pinfunction "PA5/COM5/SEG29/GPT1_CH4/COMP2_INN2_11") (pintype "passive"))
    )
    (net (code "60") (name "/S20") (class "Default")
      (node (ref "LCD1") (pin "25") (pinfunction "GEG20_25") (pintype "passive"))
      (node (ref "U9") (pin "10") (pinfunction "PA4/COM4/SEG28/GPT1_CH3/COMP2_INN1_10") (pintype "passive"))
    )
    (net (code "61") (name "/SET") (class "Default")
      (node (ref "Q8") (pin "3") (pinfunction "C_3") (pintype "passive"))
      (node (ref "U9") (pin "55") (pinfunction "PC9/SEG18/ADC_IN14/SPI2_MISO_55") (pintype "passive"))
    )
    (net (code "62") (name "/SLEEP") (class "Default")
      (node (ref "U9") (pin "24") (pinfunction "PB3/VCIN2/UART4_TX/ATIM_CH2N_24") (pintype "passive"))
    )
    (net (code "63") (name "/SWCLK") (class "Default")
      (node (ref "J2") (pin "2") (pinfunction "2_2") (pintype "passive"))
      (node (ref "R11") (pin "2") (pinfunction "2_2") (pintype "passive"))
      (node (ref "U9") (pin "78") (pinfunction "PD7/UART3_RX/SWCLK_78") (pintype "passive"))
    )
    (net (code "64") (name "/SWIO") (class "Default")
      (node (ref "J2") (pin "3") (pinfunction "3_3") (pintype "passive"))
      (node (ref "R8") (pin "2") (pinfunction "2_2") (pintype "passive"))
      (node (ref "U9") (pin "79") (pinfunction "PD8/UART3_TX/SWIO_79") (pintype "passive"))
    )
    (net (code "65") (name "/TXD5") (class "Default")
      (node (ref "U9") (pin "72") (pinfunction "PD1/SEG23/UART5_TX/ADC_IN1/GPT2_CH2_72") (pintype "passive"))
    )
    (net (code "66") (name "/VDD_XS_CTL") (class "Default")
      (node (ref "U9") (pin "73") (pinfunction "PD2/SEG24/SPI1_SSN/ADC_IN8/GPT2_CH3_73") (pintype "passive"))
    )
    (net (code "67") (name "/Vin_ADC") (class "Default")
      (node (ref "U9") (pin "53") (pinfunction "PC7/SEG16/ADC_IN6/SPI2_SSN_53") (pintype "passive"))
    )
    (net (code "68") (name "/WY_POW") (class "Default")
      (node (ref "C33") (pin "2") (pinfunction "2_2") (pintype "passive"))
      (node (ref "C64") (pin "2") (pinfunction "2_2") (pintype "passive"))
      (node (ref "P6") (pin "1") (pinfunction "1_1") (pintype "passive"))
      (node (ref "R43") (pin "1") (pinfunction "1_1") (pintype "passive"))
      (node (ref "R46") (pin "2") (pinfunction "2_2") (pintype "passive"))
      (node (ref "R97") (pin "2") (pinfunction "2_2") (pintype "passive"))
      (node (ref "TP9") (pin "1") (pinfunction "1_1") (pintype "passive"))
      (node (ref "U20") (pin "1") (pinfunction "VDDIO_1") (pintype "passive"))
      (node (ref "U20") (pin "3") (pinfunction "VDD_3") (pintype "passive"))
      (node (ref "U9") (pin "5") (pinfunction "PA15/WKUP0/SVS/COMP3_OUT_5") (pintype "passive"))
    )
    (net (code "69") (name "/WY_SCL") (class "Default")
      (node (ref "C35") (pin "1") (pinfunction "1_1") (pintype "passive"))
      (node (ref "P7") (pin "1") (pinfunction "1_1") (pintype "passive"))
      (node (ref "R46") (pin "1") (pinfunction "1_1") (pintype "passive"))
      (node (ref "TP11") (pin "1") (pinfunction "1_1") (pintype "passive"))
      (node (ref "U20") (pin "5") (pinfunction "SCL_5") (pintype "passive"))
      (node (ref "U9") (pin "2") (pinfunction "PE9/CAN_TX/ADC_IN19_2") (pintype "passive"))
    )
    (net (code "70") (name "/WY_SDA") (class "Default")
      (node (ref "C46") (pin "1") (pinfunction "1_1") (pintype "passive"))
      (node (ref "P6") (pin "2") (pinfunction "2_2") (pintype "passive"))
      (node (ref "R43") (pin "2") (pinfunction "2_2") (pintype "passive"))
      (node (ref "TP10") (pin "1") (pinfunction "1_1") (pintype "passive"))
      (node (ref "U20") (pin "6") (pinfunction "SDA_6") (pintype "passive"))
      (node (ref "U9") (pin "1") (pinfunction "PD10/CAN_RX/ADC_IN18_1") (pintype "passive"))
    )
    (net (code "71") (name "/X1") (class "Default")
      (node (ref "U9") (pin "59") (pinfunction "PH15/RTCOUT/TAMPER_59") (pintype "passive"))
    )
    (net (code "72") (name "/XS_RST") (class "Default")
      (node (ref "U9") (pin "75") (pinfunction "PD4/SEG26/SPI1_MISO/ADC_IN9/GPT2_ETR_75") (pintype "passive"))
    )
    (net (code "73") (name "/XT1") (class "Default")
      (node (ref "C42") (pin "1") (pinfunction "1_1") (pintype "passive"))
      (node (ref "U9") (pin "61") (pinfunction "XT32KI_61") (pintype "passive"))
      (node (ref "Y2") (pin "1") (pinfunction "1_1") (pintype "passive"))
    )
    (net (code "74") (name "/XT2") (class "Default")
      (node (ref "C41") (pin "2") (pinfunction "2_2") (pintype "passive"))
      (node (ref "U9") (pin "60") (pinfunction "XT32KO_60") (pintype "passive"))
      (node (ref "Y2") (pin "2") (pinfunction "2_2") (pintype "passive"))
    )
    (net (code "75") (name "3.3V") (class "Default")
      (node (ref "C27") (pin "1") (pinfunction "1_1") (pintype "passive"))
      (node (ref "C28") (pin "1") (pinfunction "1_1") (pintype "passive"))
      (node (ref "C39") (pin "2") (pinfunction "2_2") (pintype "passive"))
      (node (ref "D7") (pin "1") (pinfunction "1_1") (pintype "passive"))
      (node (ref "J2") (pin "5") (pinfunction "5_5") (pintype "passive"))
      (node (ref "Q11") (pin "2") (pinfunction "E_2") (pintype "passive"))
      (node (ref "Q12") (pin "2") (pinfunction "E_2") (pintype "passive"))
      (node (ref "Q7") (pin "2") (pinfunction "E_2") (pintype "passive"))
      (node (ref "R11") (pin "1") (pinfunction "1_1") (pintype "passive"))
      (node (ref "R42") (pin "2") (pinfunction "2_2") (pintype "passive"))
      (node (ref "R75") (pin "2") (pinfunction "2_2") (pintype "passive"))
      (node (ref "R8") (pin "1") (pinfunction "1_1") (pintype "passive"))
      (node (ref "U6") (pin "1") (pinfunction "VDD_1") (pintype "passive"))
      (node (ref "U7") (pin "1") (pinfunction "VDD_1") (pintype "passive"))
      (node (ref "U9") (pin "64") (pinfunction "VDD(VDDA)_64") (pintype "passive"))
      (node (ref "U9") (pin "66") (pinfunction "VREFP_66") (pintype "passive"))
      (node (ref "U9") (pin "67") (pinfunction "VBAT_67") (pintype "passive"))
    )
    (net (code "76") (name "GD_PWR") (class "Default")
      (node (ref "C45") (pin "1") (pinfunction "1_1") (pintype "passive"))
      (node (ref "P9") (pin "3") (pinfunction "3_3") (pintype "passive"))
      (node (ref "Q11") (pin "3") (pinfunction "C_3") (pintype "passive"))
      (node (ref "TP19") (pin "1") (pinfunction "1_1") (pintype "passive"))
    )
    (net (code "77") (name "GND") (class "Default")
      (node (ref "C26") (pin "2") (pinfunction "2_2") (pintype "passive"))
      (node (ref "C27") (pin "2") (pinfunction "2_2") (pintype "passive"))
      (node (ref "C28") (pin "2") (pinfunction "2_2") (pintype "passive"))
      (node (ref "C29") (pin "2") (pinfunction "2_2") (pintype "passive"))
      (node (ref "C30") (pin "2") (pinfunction "2_2") (pintype "passive"))
      (node (ref "C31") (pin "2") (pinfunction "2_2") (pintype "passive"))
      (node (ref "C32") (pin "2") (pinfunction "2_2") (pintype "passive"))
      (node (ref "C33") (pin "1") (pinfunction "1_1") (pintype "passive"))
      (node (ref "C35") (pin "2") (pinfunction "2_2") (pintype "passive"))
      (node (ref "C36") (pin "2") (pinfunction "2_2") (pintype "passive"))
      (node (ref "C38") (pin "2") (pinfunction "2_2") (pintype "passive"))
      (node (ref "C39") (pin "1") (pinfunction "1_1") (pintype "passive"))
      (node (ref "C41") (pin "1") (pinfunction "1_1") (pintype "passive"))
      (node (ref "C42") (pin "2") (pinfunction "2_2") (pintype "passive"))
      (node (ref "C43") (pin "2") (pinfunction "2_2") (pintype "passive"))
      (node (ref "C45") (pin "2") (pinfunction "2_2") (pintype "passive"))
      (node (ref "C46") (pin "2") (pinfunction "2_2") (pintype "passive"))
      (node (ref "C48") (pin "2") (pinfunction "2_2") (pintype "passive"))
      (node (ref "C49") (pin "2") (pinfunction "2_2") (pintype "passive"))
      (node (ref "C50") (pin "2") (pinfunction "2_2") (pintype "passive"))
      (node (ref "C56") (pin "2") (pinfunction "2_2") (pintype "passive"))
      (node (ref "C64") (pin "1") (pinfunction "1_1") (pintype "passive"))
      (node (ref "C8") (pin "2") (pinfunction "2_2") (pintype "passive"))
      (node (ref "FB2") (pin "1") (pinfunction "1_1") (pintype "passive"))
      (node (ref "J1") (pin "1") (pinfunction "1_1") (pintype "passive"))
      (node (ref "J2") (pin "4") (pinfunction "4_4") (pintype "passive"))
      (node (ref "P7") (pin "2") (pinfunction "2_2") (pintype "passive"))
      (node (ref "P9") (pin "2") (pinfunction "2_2") (pintype "passive"))
      (node (ref "Q10") (pin "2") (pinfunction "E_2") (pintype "passive"))
      (node (ref "Q5") (pin "2") (pinfunction "E_2") (pintype "passive"))
      (node (ref "Q8") (pin "2") (pinfunction "E_2") (pintype "passive"))
      (node (ref "Q9") (pin "3") (pinfunction "C_3") (pintype "passive"))
      (node (ref "R38") (pin "1") (pinfunction "1_1") (pintype "passive"))
      (node (ref "R41") (pin "1") (pinfunction "1_1") (pintype "passive"))
      (node (ref "R96") (pin "2") (pinfunction "2_2") (pintype "passive"))
      (node (ref "S1") (pin "2") (pinfunction "2_2") (pintype "passive"))
      (node (ref "TP12") (pin "1") (pinfunction "1_1") (pintype "passive"))
      (node (ref "TVS2") (pin "1") (pinfunction "1_1") (pintype "passive"))
      (node (ref "U10") (pin "4") (pinfunction "VSS_4") (pintype "passive"))
      (node (ref "U11") (pin "3") (pinfunction "GND_3") (pintype "passive"))
      (node (ref "U20") (pin "2") (pinfunction "GND_2") (pintype "passive"))
      (node (ref "U6") (pin "3") (pinfunction "GND_3") (pintype "passive"))
      (node (ref "U7") (pin "3") (pinfunction "GND_3") (pintype "passive"))
      (node (ref "U9") (pin "63") (pinfunction "VSS(VSSA)_63") (pintype "passive"))
      (node (ref "U9") (pin "65") (pinfunction "VREFN_65") (pintype "passive"))
    )
    (net (code "78") (name "Net-(B1-+)") (class "Default")
      (node (ref "B1") (pin "1") (pinfunction "+_1") (pintype "passive"))
      (node (ref "R42") (pin "1") (pinfunction "1_1") (pintype "passive"))
    )
    (net (code "79") (name "Net-(B1--)") (class "Default")
      (node (ref "B1") (pin "2") (pinfunction "-_2") (pintype "passive"))
      (node (ref "Q5") (pin "3") (pinfunction "C_3") (pintype "passive"))
    )
    (net (code "80") (name "Net-(D5-K)") (class "Default")
      (node (ref "D5") (pin "2") (pinfunction "K_2") (pintype "passive"))
      (node (ref "R35") (pin "2") (pinfunction "2_2") (pintype "passive"))
    )
    (net (code "81") (name "Net-(D6-A)") (class "Default")
      (node (ref "D6") (pin "1") (pinfunction "A_1") (pintype "passive"))
      (node (ref "R39") (pin "2") (pinfunction "2_2") (pintype "passive"))
    )
    (net (code "82") (name "Net-(D7-Pad2)") (class "Default")
      (node (ref "D7") (pin "2") (pinfunction "2_2") (pintype "passive"))
      (node (ref "R7") (pin "2") (pinfunction "2_2") (pintype "passive"))
    )
    (net (code "83") (name "Net-(D10-A-Pad1)") (class "Default")
      (node (ref "D10") (pin "1") (pinfunction "A_1") (pintype "passive"))
      (node (ref "D10") (pin "2") (pinfunction "A_2") (pintype "passive"))
      (node (ref "FB1") (pin "2") (pinfunction "2_2") (pintype "passive"))
    )
    (net (code "84") (name "Net-(D10-C)") (class "Default")
      (node (ref "D10") (pin "3") (pinfunction "C_3") (pintype "passive"))
      (node (ref "P10") (pin "2") (pinfunction "2_2") (pintype "passive"))
      (node (ref "P5") (pin "2") (pinfunction "2_2") (pintype "passive"))
      (node (ref "TVS2") (pin "2") (pinfunction "2_2") (pintype "passive"))
    )
    (net (code "85") (name "Net-(FB2-Pad2)") (class "Default")
      (node (ref "FB2") (pin "2") (pinfunction "2_2") (pintype "passive"))
      (node (ref "P10") (pin "1") (pinfunction "1_1") (pintype "passive"))
      (node (ref "P5") (pin "1") (pinfunction "1_1") (pintype "passive"))
    )
    (net (code "86") (name "Net-(J1-Pad2)") (class "Default")
      (node (ref "J1") (pin "2") (pinfunction "2_2") (pintype "passive"))
      (node (ref "R37") (pin "1") (pinfunction "1_1") (pintype "passive"))
    )
    (net (code "87") (name "Net-(J1-Pad3)") (class "Default")
      (node (ref "J1") (pin "3") (pinfunction "3_3") (pintype "passive"))
      (node (ref "R36") (pin "1") (pinfunction "1_1") (pintype "passive"))
    )
    (net (code "88") (name "Net-(J1-Pad4)") (class "Default")
      (node (ref "J1") (pin "4") (pinfunction "4_4") (pintype "passive"))
      (node (ref "R31") (pin "1") (pinfunction "1_1") (pintype "passive"))
    )
    (net (code "89") (name "Net-(J2-Pad1)") (class "Default")
      (node (ref "J2") (pin "1") (pinfunction "1_1") (pintype "passive"))
      (node (ref "R1") (pin "2") (pinfunction "2_2") (pintype "passive"))
    )
    (net (code "90") (name "Net-(Q5-B)") (class "Default")
      (node (ref "Q5") (pin "1") (pinfunction "B_1") (pintype "passive"))
      (node (ref "R47") (pin "2") (pinfunction "2_2") (pintype "passive"))
    )
    (net (code "91") (name "Net-(Q7-B)") (class "Default")
      (node (ref "Q7") (pin "1") (pinfunction "B_1") (pintype "passive"))
      (node (ref "R27") (pin "2") (pinfunction "2_2") (pintype "passive"))
    )
    (net (code "92") (name "Net-(Q8-B)") (class "Default")
      (node (ref "Q8") (pin "1") (pinfunction "B_1") (pintype "passive"))
      (node (ref "R31") (pin "2") (pinfunction "2_2") (pintype "passive"))
      (node (ref "R38") (pin "2") (pinfunction "2_2") (pintype "passive"))
    )
    (net (code "93") (name "Net-(Q9-B)") (class "Default")
      (node (ref "Q9") (pin "1") (pinfunction "B_1") (pintype "passive"))
      (node (ref "R40") (pin "2") (pinfunction "2_2") (pintype "passive"))
    )
    (net (code "94") (name "Net-(Q9-E)") (class "Default")
      (node (ref "Q9") (pin "2") (pinfunction "E_2") (pintype "passive"))
      (node (ref "R35") (pin "1") (pinfunction "1_1") (pintype "passive"))
    )
    (net (code "95") (name "Net-(Q10-B)") (class "Default")
      (node (ref "C32") (pin "1") (pinfunction "1_1") (pintype "passive"))
      (node (ref "Q10") (pin "1") (pinfunction "B_1") (pintype "passive"))
      (node (ref "R39") (pin "1") (pinfunction "1_1") (pintype "passive"))
      (node (ref "R41") (pin "2") (pinfunction "2_2") (pintype "passive"))
    )
    (net (code "96") (name "Net-(Q11-B)") (class "Default")
      (node (ref "Q11") (pin "1") (pinfunction "B_1") (pintype "passive"))
      (node (ref "R3") (pin "2") (pinfunction "2_2") (pintype "passive"))
    )
    (net (code "97") (name "Net-(Q12-B)") (class "Default")
      (node (ref "Q12") (pin "1") (pinfunction "B_1") (pintype "passive"))
      (node (ref "R49") (pin "2") (pinfunction "2_2") (pintype "passive"))
    )
    (net (code "98") (name "Net-(Q12-C)") (class "Default")
      (node (ref "C36") (pin "1") (pinfunction "1_1") (pintype "passive"))
      (node (ref "Q12") (pin "3") (pinfunction "C_3") (pintype "passive"))
      (node (ref "U10") (pin "3") (pinfunction "WP#_3") (pintype "passive"))
      (node (ref "U10") (pin "7") (pinfunction "HOLD#_7") (pintype "passive"))
      (node (ref "U10") (pin "8") (pinfunction "VDD_8") (pintype "passive"))
    )
    (net (code "99") (name "Net-(U9-VDD15)") (class "Default")
      (node (ref "C38") (pin "1") (pinfunction "1_1") (pintype "passive"))
      (node (ref "U9") (pin "62") (pinfunction "VDD15_62") (pintype "passive"))
    )
    (net (code "100") (name "Net-(U20-SDO)") (class "Default")
      (node (ref "R96") (pin "1") (pinfunction "1_1") (pintype "passive"))
      (node (ref "R97") (pin "1") (pinfunction "1_1") (pintype "passive"))
      (node (ref "U20") (pin "8") (pinfunction "SDO_8") (pintype "passive"))
    )
    (net (code "101") (name "unconnected-(U9-PC15{slash}SEG42{slash}LPT32_CH3{slash}CAN_RX-Pad42)") (class "Default")
      (node (ref "U9") (pin "42") (pinfunction "PC15/SEG42/LPT32_CH3/CAN_RX_42") (pintype "passive+no_connect"))
    )
    (net (code "102") (name "unconnected-(U20-CSB-Pad7)") (class "Default")
      (node (ref "U20") (pin "7") (pinfunction "CSB_7") (pintype "passive"))
    )
    (net (code "103") (name "unconnected-(U20-NC-Pad4)") (class "Default")
      (node (ref "U20") (pin "4") (pinfunction "NC_4") (pintype "passive+no_connect"))
    )
  )
)
